# DM0249_BW235_IMX378.net
KiCad netlist of a schematic drawn in Altium Designer
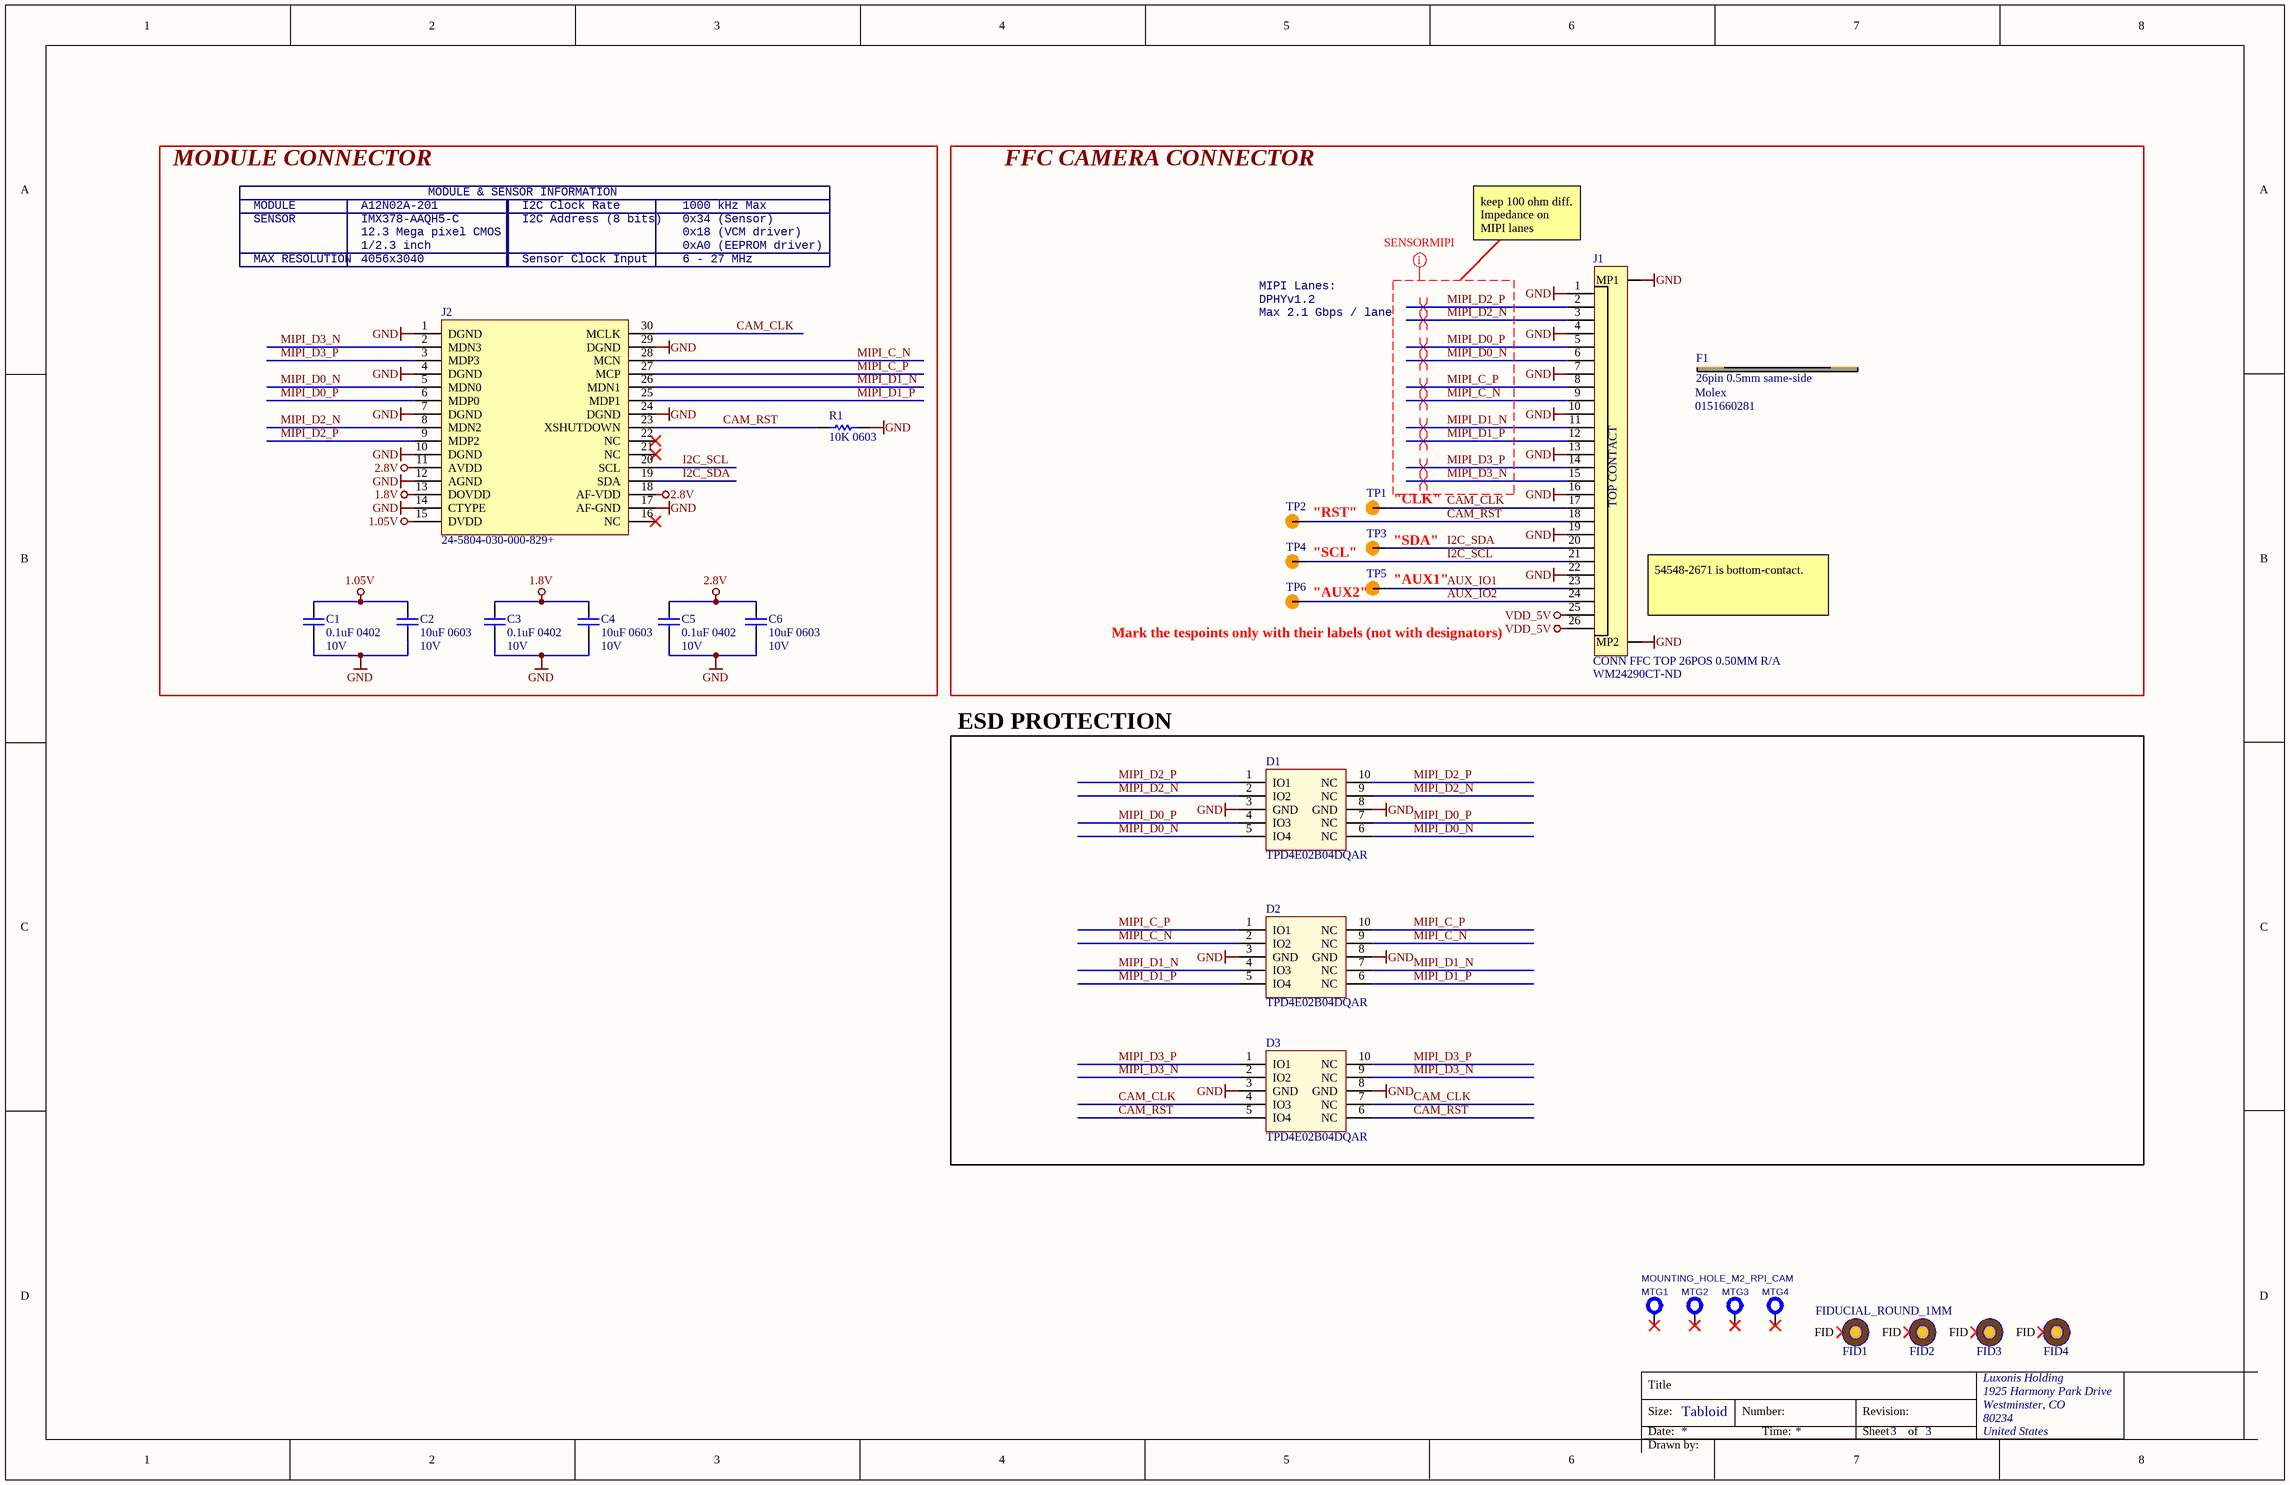
[diagram p0: DM0249_BW235_IMX378.SchDoc]

(export (version "E")
  (design (tool "Eeschema 10.0.6"))
  (components
    (comp (ref "C1")
      (value "0.1uF 0402")
      (footprint "CAP_Altium_Vault_Generic:CAPC0402(1005)70_N")
      (description "CAP CER 0.1UF 10V X7R 0402 5%")
      (fields (field (name "TOLERANCE") "5%") (field (name "VOLTAGE RATING") "10V"))
      (libsource (lib "LuxonisMaster") (part "GRM155R71A104JA01D"))
    )
    (comp (ref "C2")
      (value "10uF 0603")
      (footprint "CAP_Altium_Vault_Generic:CAPC0603(1608)100_N")
      (description "CAP CER 10UF 10V X5R 0603 20%")
      (fields (field (name "TOLERANCE") "20%") (field (name "VOLTAGE RATING") "10V"))
      (libsource (lib "LuxonisMaster") (part "GRM188R61A106ME69D"))
    )
    (comp (ref "C3")
      (value "0.1uF 0402")
      (footprint "CAP_Altium_Vault_Generic:CAPC0402(1005)70_N")
      (description "CAP CER 0.1UF 10V X7R 0402 5%")
      (fields (field (name "TOLERANCE") "5%") (field (name "VOLTAGE RATING") "10V"))
      (libsource (lib "LuxonisMaster") (part "GRM155R71A104JA01D"))
    )
    (comp (ref "C4")
      (value "10uF 0603")
      (footprint "CAP_Altium_Vault_Generic:CAPC0603(1608)100_N")
      (description "CAP CER 10UF 10V X5R 0603 20%")
      (fields (field (name "TOLERANCE") "20%") (field (name "VOLTAGE RATING") "10V"))
      (libsource (lib "LuxonisMaster") (part "GRM188R61A106ME69D"))
    )
    (comp (ref "C5")
      (value "0.1uF 0402")
      (footprint "CAP_Altium_Vault_Generic:CAPC0402(1005)70_N")
      (description "CAP CER 0.1UF 10V X7R 0402 5%")
      (fields (field (name "TOLERANCE") "5%") (field (name "VOLTAGE RATING") "10V"))
      (libsource (lib "LuxonisMaster") (part "GRM155R71A104JA01D"))
    )
    (comp (ref "C6")
      (value "10uF 0603")
      (footprint "CAP_Altium_Vault_Generic:CAPC0603(1608)100_N")
      (description "CAP CER 10UF 10V X5R 0603 20%")
      (fields (field (name "TOLERANCE") "20%") (field (name "VOLTAGE RATING") "10V"))
      (libsource (lib "LuxonisMaster") (part "GRM188R61A106ME69D"))
    )
    (comp (ref "D1")
      (value "TPD4E02B04DQAR")
      (footprint "LuxonisMaster:TPD4E02B04DQAR")
      (libsource (lib "LuxonisMaster") (part "TPD4E02B04DQAR"))
    )
    (comp (ref "D2")
      (value "TPD4E02B04DQAR")
      (footprint "LuxonisMaster:TPD4E02B04DQAR")
      (libsource (lib "LuxonisMaster") (part "TPD4E02B04DQAR"))
    )
    (comp (ref "D3")
      (value "TPD4E02B04DQAR")
      (footprint "LuxonisMaster:TPD4E02B04DQAR")
      (libsource (lib "LuxonisMaster") (part "TPD4E02B04DQAR"))
    )
    (comp (ref "F1")
      (value "26pin 0.5mm same-side")
      (description "CABLE FFC 26POS 0.50MM 6\"")
      (fields
        (field (name "MANUFACTURER 1") "Molex")
        (field (name "MANUFACTURER PART NUMBER 1") "0151660281")
      )
      (libsource (lib "BG0249_R1M1E1") (part "0151660281"))
    )
    (comp (ref "FID1")
      (value "FIDUCIAL_ROUND_1MM")
      (footprint "LuxonisMaster:FIDUCIAL_ROUND_1MM")
      (description "Fiducial with various available footprints")
      (libsource (lib "LuxonisMaster") (part "FIDUCIAL"))
    )
    (comp (ref "FID2")
      (value "FIDUCIAL_ROUND_1MM")
      (footprint "LuxonisMaster:FIDUCIAL_ROUND_1MM")
      (description "Fiducial with various available footprints")
      (libsource (lib "LuxonisMaster") (part "FIDUCIAL"))
    )
    (comp (ref "FID3")
      (value "FIDUCIAL_ROUND_1MM")
      (footprint "LuxonisMaster:FIDUCIAL_ROUND_1MM")
      (description "Fiducial with various available footprints")
      (libsource (lib "LuxonisMaster") (part "FIDUCIAL"))
    )
    (comp (ref "FID4")
      (value "FIDUCIAL_ROUND_1MM")
      (footprint "LuxonisMaster:FIDUCIAL_ROUND_1MM")
      (description "Fiducial with various available footprints")
      (libsource (lib "LuxonisMaster") (part "FIDUCIAL"))
    )
    (comp (ref "J1")
      (value "CONN FFC TOP 26POS 0.50MM R/A")
      (footprint "5052782633")
      (description "0.5 Ffc Zif Btm Cont Embt Pkg 0.5 Fpc Zif Btm FS19")
      (fields
        (field (name "MANUFACTURER") "Molex")
        (field (name "MANUFACTURER PART NUMBER") "505278-2633")
        (field (name "SUPPLIER PART NUMBER 1") "WM24290CT-ND")
      )
      (libsource (lib "DM1098FFC") (part "5052782633"))
    )
    (comp (ref "J2")
      (value "24-5804-030-000-829+")
      (footprint "DM1092_R0M0E0:A12N02A-201_1.6mmbrd_MatedModule")
      (description "CONN Series 5804 board to board 0.4mm pitch 30 way connector")
      (libsource (lib "DM1092_R0M0E0") (part "A12N02A-201_Connector_(1.6mm_brd)"))
    )
    (comp (ref "MTG1")
      (value "MOUNTING_HOLE_M2_RPI_CAM")
      (footprint "LuxonisMaster:MOUNTING_HOLE_M2_RPI_CAM")
      (description "=CurrentFootprint")
      (libsource (lib "LuxonisMaster") (part "MP_Mounting-Holes"))
    )
    (comp (ref "MTG2")
      (value "MOUNTING_HOLE_M2_RPI_CAM")
      (footprint "LuxonisMaster:MOUNTING_HOLE_M2_RPI_CAM")
      (description "=CurrentFootprint")
      (libsource (lib "LuxonisMaster") (part "MP_Mounting-Holes"))
    )
    (comp (ref "MTG3")
      (value "MOUNTING_HOLE_M2_RPI_CAM")
      (footprint "LuxonisMaster:MOUNTING_HOLE_M2_RPI_CAM")
      (description "=CurrentFootprint")
      (libsource (lib "LuxonisMaster") (part "MP_Mounting-Holes"))
    )
    (comp (ref "MTG4")
      (value "MOUNTING_HOLE_M2_RPI_CAM")
      (footprint "LuxonisMaster:MOUNTING_HOLE_M2_RPI_CAM")
      (description "=CurrentFootprint")
      (libsource (lib "LuxonisMaster") (part "MP_Mounting-Holes"))
    )
    (comp (ref "R1")
      (value "10K 0603")
      (footprint "RES_Altium_Vault_Generic:RESC0603(1608)_N")
      (description "RES SMD 10K OHM 1% 1/10W 0603")
      (fields (field (name "TOLERANCE") "1%"))
      (libsource (lib "LuxonisMaster") (part "RC0603FR-0710KL"))
    )
    (comp (ref "TP1")
      (value "TP100_150_NS")
      (footprint "LuxonisMaster:TP100_150_NS")
      (libsource (lib "LuxonisMaster") (part "TEST_POINT"))
    )
    (comp (ref "TP2")
      (value "TP100_150_NS")
      (footprint "LuxonisMaster:TP100_150_NS")
      (libsource (lib "LuxonisMaster") (part "TEST_POINT"))
    )
    (comp (ref "TP3")
      (value "TP100_150_NS")
      (footprint "LuxonisMaster:TP100_150_NS")
      (libsource (lib "LuxonisMaster") (part "TEST_POINT"))
    )
    (comp (ref "TP4")
      (value "TP100_150_NS")
      (footprint "LuxonisMaster:TP100_150_NS")
      (libsource (lib "LuxonisMaster") (part "TEST_POINT"))
    )
    (comp (ref "TP5")
      (value "TP100_150_NS")
      (footprint "LuxonisMaster:TP100_150_NS")
      (libsource (lib "LuxonisMaster") (part "TEST_POINT"))
    )
    (comp (ref "TP6")
      (value "TP100_150_NS")
      (footprint "LuxonisMaster:TP100_150_NS")
      (libsource (lib "LuxonisMaster") (part "TEST_POINT"))
    )
  )
  (nets
    (net (code "1") (name "/AUX_IO1") (class "Default")
      (node (ref "J1") (pin "23") (pinfunction "23_23") (pintype "passive"))
      (node (ref "TP5") (pin "1") (pintype "passive"))
    )
    (net (code "2") (name "/AUX_IO2") (class "Default")
      (node (ref "J1") (pin "24") (pinfunction "24_24") (pintype "passive"))
      (node (ref "TP6") (pin "1") (pintype "passive"))
    )
    (net (code "3") (name "/CAM_CLK") (class "Default")
      (node (ref "D3") (pin "4") (pinfunction "IO3_4") (pintype "passive"))
      (node (ref "D3") (pin "7") (pinfunction "NC_7") (pintype "passive"))
      (node (ref "J1") (pin "17") (pinfunction "17_17") (pintype "passive"))
      (node (ref "J2") (pin "30") (pinfunction "MCLK_30") (pintype "passive"))
      (node (ref "TP1") (pin "1") (pintype "passive"))
    )
    (net (code "4") (name "/CAM_RST") (class "Default")
      (node (ref "D3") (pin "5") (pinfunction "IO4_5") (pintype "passive"))
      (node (ref "D3") (pin "6") (pinfunction "NC_6") (pintype "passive"))
      (node (ref "J1") (pin "18") (pinfunction "18_18") (pintype "passive"))
      (node (ref "J2") (pin "23") (pinfunction "XSHUTDOWN_23") (pintype "passive"))
      (node (ref "R1") (pin "1") (pinfunction "1_1") (pintype "passive"))
      (node (ref "TP2") (pin "1") (pintype "passive"))
    )
    (net (code "5") (name "/I2C_SCL") (class "Default")
      (node (ref "J1") (pin "21") (pinfunction "21_21") (pintype "passive"))
      (node (ref "J2") (pin "20") (pinfunction "SCL_20") (pintype "passive"))
      (node (ref "TP4") (pin "1") (pintype "passive"))
    )
    (net (code "6") (name "/I2C_SDA") (class "Default")
      (node (ref "J1") (pin "20") (pinfunction "20_20") (pintype "passive"))
      (node (ref "J2") (pin "19") (pinfunction "SDA_19") (pintype "passive"))
      (node (ref "TP3") (pin "1") (pintype "passive"))
    )
    (net (code "7") (name "/MIPI_C_N") (class "Default")
      (node (ref "D2") (pin "2") (pinfunction "IO2_2") (pintype "passive"))
      (node (ref "D2") (pin "9") (pinfunction "NC_9") (pintype "passive"))
      (node (ref "J1") (pin "9") (pinfunction "9_9") (pintype "passive"))
      (node (ref "J2") (pin "28") (pinfunction "MCN_28") (pintype "passive"))
    )
    (net (code "8") (name "/MIPI_C_P") (class "Default")
      (node (ref "D2") (pin "1") (pinfunction "IO1_1") (pintype "passive"))
      (node (ref "D2") (pin "10") (pinfunction "NC_10") (pintype "passive"))
      (node (ref "J1") (pin "8") (pinfunction "8_8") (pintype "passive"))
      (node (ref "J2") (pin "27") (pinfunction "MCP_27") (pintype "passive"))
    )
    (net (code "9") (name "/MIPI_D0_N") (class "Default")
      (node (ref "D1") (pin "5") (pinfunction "IO4_5") (pintype "passive"))
      (node (ref "D1") (pin "6") (pinfunction "NC_6") (pintype "passive"))
      (node (ref "J1") (pin "6") (pinfunction "6_6") (pintype "passive"))
      (node (ref "J2") (pin "5") (pinfunction "MDN0_5") (pintype "passive"))
    )
    (net (code "10") (name "/MIPI_D0_P") (class "Default")
      (node (ref "D1") (pin "4") (pinfunction "IO3_4") (pintype "passive"))
      (node (ref "D1") (pin "7") (pinfunction "NC_7") (pintype "passive"))
      (node (ref "J1") (pin "5") (pinfunction "5_5") (pintype "passive"))
      (node (ref "J2") (pin "6") (pinfunction "MDP0_6") (pintype "passive"))
    )
    (net (code "11") (name "/MIPI_D1_N") (class "Default")
      (node (ref "D2") (pin "4") (pinfunction "IO3_4") (pintype "passive"))
      (node (ref "D2") (pin "7") (pinfunction "NC_7") (pintype "passive"))
      (node (ref "J1") (pin "11") (pinfunction "11_11") (pintype "passive"))
      (node (ref "J2") (pin "26") (pinfunction "MDN1_26") (pintype "passive"))
    )
    (net (code "12") (name "/MIPI_D1_P") (class "Default")
      (node (ref "D2") (pin "5") (pinfunction "IO4_5") (pintype "passive"))
      (node (ref "D2") (pin "6") (pinfunction "NC_6") (pintype "passive"))
      (node (ref "J1") (pin "12") (pinfunction "12_12") (pintype "passive"))
      (node (ref "J2") (pin "25") (pinfunction "MDP1_25") (pintype "passive"))
    )
    (net (code "13") (name "/MIPI_D2_N") (class "Default")
      (node (ref "D1") (pin "2") (pinfunction "IO2_2") (pintype "passive"))
      (node (ref "D1") (pin "9") (pinfunction "NC_9") (pintype "passive"))
      (node (ref "J1") (pin "3") (pinfunction "3_3") (pintype "passive"))
      (node (ref "J2") (pin "8") (pinfunction "MDN2_8") (pintype "passive"))
    )
    (net (code "14") (name "/MIPI_D2_P") (class "Default")
      (node (ref "D1") (pin "1") (pinfunction "IO1_1") (pintype "passive"))
      (node (ref "D1") (pin "10") (pinfunction "NC_10") (pintype "passive"))
      (node (ref "J1") (pin "2") (pinfunction "2_2") (pintype "passive"))
      (node (ref "J2") (pin "9") (pinfunction "MDP2_9") (pintype "passive"))
    )
    (net (code "15") (name "/MIPI_D3_N") (class "Default")
      (node (ref "D3") (pin "2") (pinfunction "IO2_2") (pintype "passive"))
      (node (ref "D3") (pin "9") (pinfunction "NC_9") (pintype "passive"))
      (node (ref "J1") (pin "15") (pinfunction "15_15") (pintype "passive"))
      (node (ref "J2") (pin "2") (pinfunction "MDN3_2") (pintype "passive"))
    )
    (net (code "16") (name "/MIPI_D3_P") (class "Default")
      (node (ref "D3") (pin "1") (pinfunction "IO1_1") (pintype "passive"))
      (node (ref "D3") (pin "10") (pinfunction "NC_10") (pintype "passive"))
      (node (ref "J1") (pin "14") (pinfunction "14_14") (pintype "passive"))
      (node (ref "J2") (pin "3") (pinfunction "MDP3_3") (pintype "passive"))
    )
    (net (code "17") (name "1.05V") (class "Default")
      (node (ref "C1") (pin "2") (pinfunction "2_2") (pintype "passive"))
      (node (ref "C2") (pin "2") (pinfunction "2_2") (pintype "passive"))
      (node (ref "J2") (pin "15") (pinfunction "DVDD_15") (pintype "passive"))
    )
    (net (code "18") (name "1.8V") (class "Default")
      (node (ref "C3") (pin "2") (pinfunction "2_2") (pintype "passive"))
      (node (ref "C4") (pin "2") (pinfunction "2_2") (pintype "passive"))
      (node (ref "J2") (pin "13") (pinfunction "DOVDD_13") (pintype "passive"))
    )
    (net (code "19") (name "2.8V") (class "Default")
      (node (ref "C5") (pin "2") (pinfunction "2_2") (pintype "passive"))
      (node (ref "C6") (pin "2") (pinfunction "2_2") (pintype "passive"))
      (node (ref "J2") (pin "11") (pinfunction "AVDD_11") (pintype "passive"))
      (node (ref "J2") (pin "18") (pinfunction "AF-VDD_18") (pintype "passive"))
    )
    (net (code "20") (name "GND") (class "Default")
      (node (ref "C1") (pin "1") (pinfunction "1_1") (pintype "passive"))
      (node (ref "C2") (pin "1") (pinfunction "1_1") (pintype "passive"))
      (node (ref "C3") (pin "1") (pinfunction "1_1") (pintype "passive"))
      (node (ref "C4") (pin "1") (pinfunction "1_1") (pintype "passive"))
      (node (ref "C5") (pin "1") (pinfunction "1_1") (pintype "passive"))
      (node (ref "C6") (pin "1") (pinfunction "1_1") (pintype "passive"))
      (node (ref "D1") (pin "3") (pinfunction "GND_3") (pintype "passive"))
      (node (ref "D1") (pin "8") (pinfunction "GND_8") (pintype "passive"))
      (node (ref "D2") (pin "3") (pinfunction "GND_3") (pintype "passive"))
      (node (ref "D2") (pin "8") (pinfunction "GND_8") (pintype "passive"))
      (node (ref "D3") (pin "3") (pinfunction "GND_3") (pintype "passive"))
      (node (ref "D3") (pin "8") (pinfunction "GND_8") (pintype "passive"))
      (node (ref "J1") (pin "1") (pinfunction "1_1") (pintype "passive"))
      (node (ref "J1") (pin "10") (pinfunction "10_10") (pintype "passive"))
      (node (ref "J1") (pin "13") (pinfunction "13_13") (pintype "passive"))
      (node (ref "J1") (pin "16") (pinfunction "16_16") (pintype "passive"))
      (node (ref "J1") (pin "19") (pinfunction "19_19") (pintype "passive"))
      (node (ref "J1") (pin "22") (pinfunction "22_22") (pintype "passive"))
      (node (ref "J1") (pin "4") (pinfunction "4_4") (pintype "passive"))
      (node (ref "J1") (pin "7") (pinfunction "7_7") (pintype "passive"))
      (node (ref "J1") (pin "MP1") (pinfunction "MP1_MP1") (pintype "passive"))
      (node (ref "J1") (pin "MP2") (pinfunction "MP2_MP2") (pintype "passive"))
      (node (ref "J2") (pin "1") (pinfunction "DGND_1") (pintype "passive"))
      (node (ref "J2") (pin "10") (pinfunction "DGND_10") (pintype "passive"))
      (node (ref "J2") (pin "12") (pinfunction "AGND_12") (pintype "passive"))
      (node (ref "J2") (pin "14") (pinfunction "CTYPE_14") (pintype "passive"))
      (node (ref "J2") (pin "17") (pinfunction "AF-GND_17") (pintype "passive"))
      (node (ref "J2") (pin "24") (pinfunction "DGND_24") (pintype "passive"))
      (node (ref "J2") (pin "29") (pinfunction "DGND_29") (pintype "passive"))
      (node (ref "J2") (pin "4") (pinfunction "DGND_4") (pintype "passive"))
      (node (ref "J2") (pin "7") (pinfunction "DGND_7") (pintype "passive"))
      (node (ref "R1") (pin "2") (pinfunction "2_2") (pintype "passive"))
    )
    (net (code "21") (name "VDD_5V") (class "Default")
      (node (ref "J1") (pin "25") (pinfunction "25_25") (pintype "passive"))
      (node (ref "J1") (pin "26") (pinfunction "26_26") (pintype "passive"))
    )
    (net (code "22") (name "unconnected-(FID1-PadFID)") (class "Default")
      (node (ref "FID1") (pin "FID") (pinfunction "FID_FID") (pintype "input+no_connect"))
    )
    (net (code "23") (name "unconnected-(FID2-PadFID)") (class "Default")
      (node (ref "FID2") (pin "FID") (pinfunction "FID_FID") (pintype "input+no_connect"))
    )
    (net (code "24") (name "unconnected-(FID3-PadFID)") (class "Default")
      (node (ref "FID3") (pin "FID") (pinfunction "FID_FID") (pintype "input+no_connect"))
    )
    (net (code "25") (name "unconnected-(FID4-PadFID)") (class "Default")
      (node (ref "FID4") (pin "FID") (pinfunction "FID_FID") (pintype "input+no_connect"))
    )
    (net (code "26") (name "unconnected-(J2-NC-Pad16)") (class "Default")
      (node (ref "J2") (pin "16") (pinfunction "NC_16") (pintype "passive+no_connect"))
    )
    (net (code "27") (name "unconnected-(J2-NC-Pad21)") (class "Default")
      (node (ref "J2") (pin "21") (pinfunction "NC_21") (pintype "passive+no_connect"))
    )
    (net (code "28") (name "unconnected-(J2-NC-Pad22)") (class "Default")
      (node (ref "J2") (pin "22") (pinfunction "NC_22") (pintype "passive+no_connect"))
    )
    (net (code "29") (name "unconnected-(MTG1-Pad1)") (class "Default")
      (node (ref "MTG1") (pin "1") (pintype "passive+no_connect"))
    )
    (net (code "30") (name "unconnected-(MTG2-Pad1)") (class "Default")
      (node (ref "MTG2") (pin "1") (pintype "passive+no_connect"))
    )
    (net (code "31") (name "unconnected-(MTG3-Pad1)") (class "Default")
      (node (ref "MTG3") (pin "1") (pintype "passive+no_connect"))
    )
    (net (code "32") (name "unconnected-(MTG4-Pad1)") (class "Default")
      (node (ref "MTG4") (pin "1") (pintype "passive+no_connect"))
    )
  )
)
